# main.net
KiCad netlist of a schematic drawn in Altium Designer
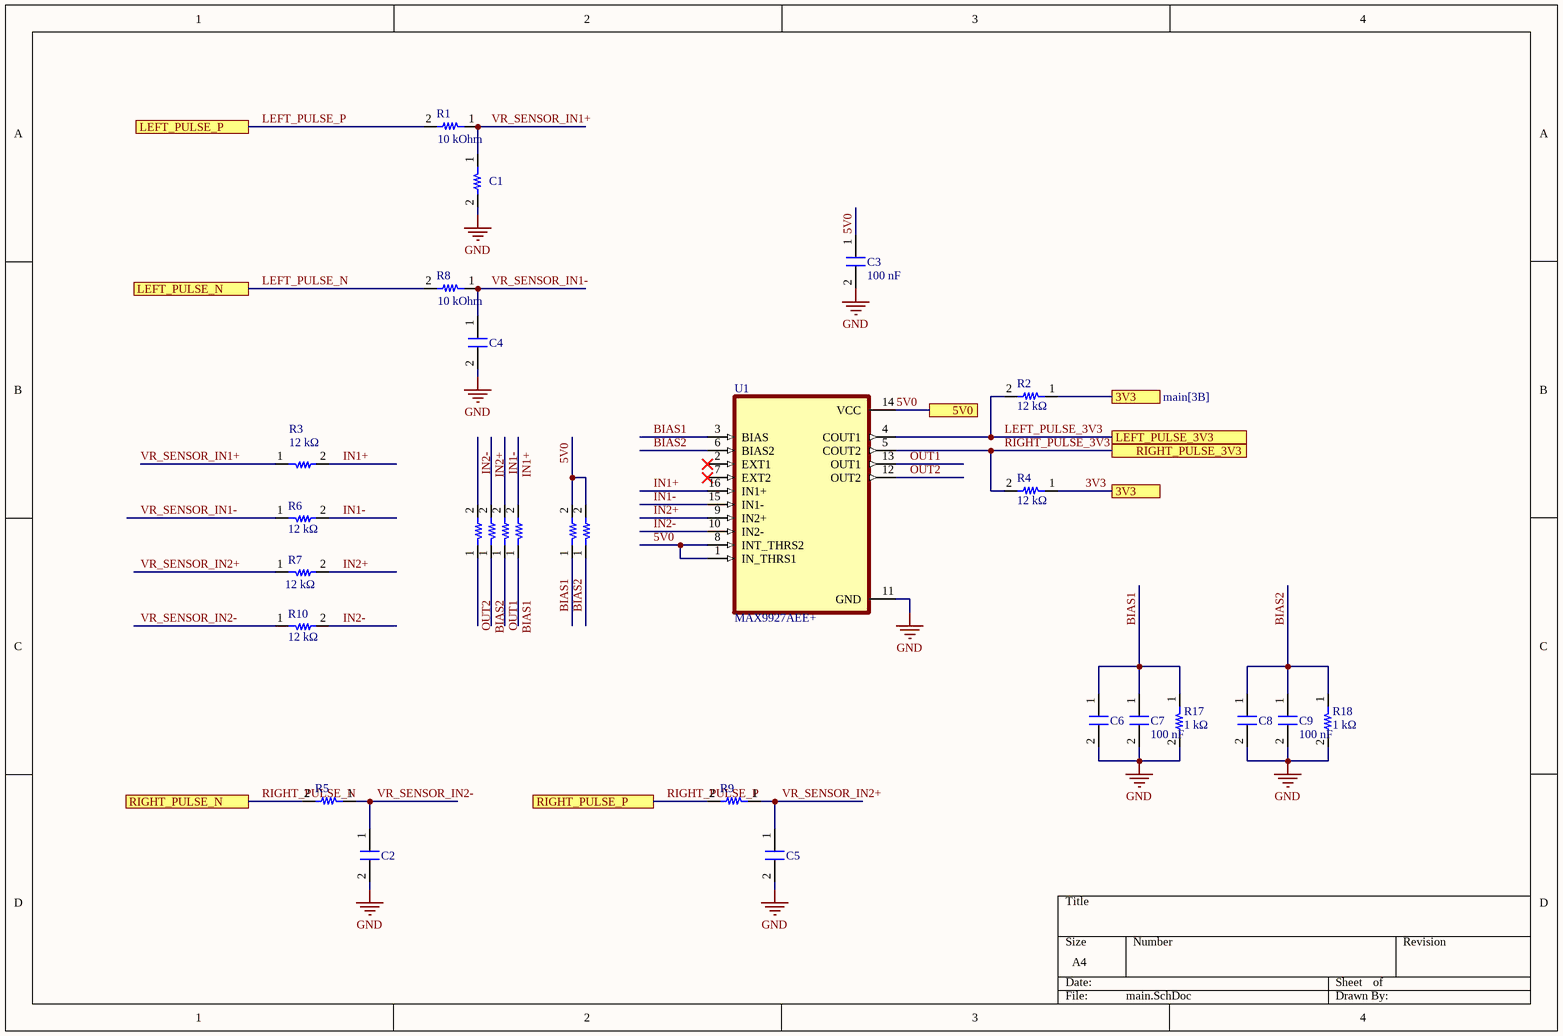
[diagram p0: main.SchDoc]

(export (version "E")
  (design (tool "Eeschema 10.0.6"))
  (components
    (comp (ref "C1")
      (value "Resistor_0402")
      (footprint "0402_fp")
      (libsource (lib "RC_sch") (part "Resistor_0402"))
    )
    (comp (ref "C2")
      (value "Capacitor_0402")
      (footprint "0402_fp")
      (libsource (lib "RC_sch") (part "Capacitor_0402"))
    )
    (comp (ref "C3")
      (value "100 nF")
      (footprint "0402_fp")
      (fields (field (name "Comment") "Capacitor_0402"))
      (libsource (lib "RC_sch") (part "Capacitor_0402"))
    )
    (comp (ref "C4")
      (value "Capacitor_0402")
      (footprint "0402_fp")
      (libsource (lib "RC_sch") (part "Capacitor_0402"))
    )
    (comp (ref "C5")
      (value "Capacitor_0402")
      (footprint "0402_fp")
      (libsource (lib "RC_sch") (part "Capacitor_0402"))
    )
    (comp (ref "C6")
      (value "Capacitor_0603")
      (footprint "0603_FP")
      (libsource (lib "RC_sch") (part "Capacitor_0603"))
    )
    (comp (ref "C7")
      (value "100 nF")
      (footprint "0402_fp")
      (fields (field (name "Comment") "Capacitor_0402"))
      (libsource (lib "RC_sch") (part "Capacitor_0402"))
    )
    (comp (ref "C8")
      (value "Capacitor_0603")
      (footprint "0603_FP")
      (libsource (lib "RC_sch") (part "Capacitor_0603"))
    )
    (comp (ref "C9")
      (value "100 nF")
      (footprint "0402_fp")
      (fields (field (name "Comment") "Capacitor_0402"))
      (libsource (lib "RC_sch") (part "Capacitor_0402"))
    )
    (comp (ref "R1")
      (value "10 kOhm")
      (footprint "0402_fp")
      (fields (field (name "Comment") "Resistor_0402"))
      (libsource (lib "RC_sch") (part "Resistor_0402"))
    )
    (comp (ref "R2")
      (value "12 kΩ")
      (footprint "0402_fp")
      (fields (field (name "Comment") "Resistor_0402"))
      (libsource (lib "RC_sch") (part "Resistor_0402"))
    )
    (comp (ref "R3")
      (value "12 kΩ")
      (footprint "0402_fp")
      (fields (field (name "Comment") "Resistor_0402"))
      (libsource (lib "RC_sch") (part "Resistor_0402"))
    )
    (comp (ref "R4")
      (value "12 kΩ")
      (footprint "0402_fp")
      (fields (field (name "Comment") "Resistor_0402"))
      (libsource (lib "RC_sch") (part "Resistor_0402"))
    )
    (comp (ref "R5")
      (value "Resistor_0402")
      (footprint "0402_fp")
      (libsource (lib "RC_sch") (part "Resistor_0402"))
    )
    (comp (ref "R6")
      (value "12 kΩ")
      (footprint "0402_fp")
      (fields (field (name "Comment") "Resistor_0402"))
      (libsource (lib "RC_sch") (part "Resistor_0402"))
    )
    (comp (ref "R7")
      (value "12 kΩ")
      (footprint "0402_fp")
      (fields (field (name "Comment") "Resistor_0402"))
      (libsource (lib "RC_sch") (part "Resistor_0402"))
    )
    (comp (ref "R8")
      (value "10 kOhm")
      (footprint "0402_fp")
      (fields (field (name "Comment") "Resistor_0402"))
      (libsource (lib "RC_sch") (part "Resistor_0402"))
    )
    (comp (ref "R9")
      (value "Resistor_0402")
      (footprint "0402_fp")
      (libsource (lib "RC_sch") (part "Resistor_0402"))
    )
    (comp (ref "R10")
      (value "12 kΩ")
      (footprint "0402_fp")
      (fields (field (name "Comment") "Resistor_0402"))
      (libsource (lib "RC_sch") (part "Resistor_0402"))
    )
    (comp (ref "R11")
      (value "Resistor_0402")
      (footprint "0402_fp")
      (libsource (lib "RC_sch") (part "Resistor_0402"))
    )
    (comp (ref "R12")
      (value "Resistor_0402")
      (footprint "0402_fp")
      (libsource (lib "RC_sch") (part "Resistor_0402"))
    )
    (comp (ref "R13")
      (value "Resistor_0402")
      (footprint "0402_fp")
      (libsource (lib "RC_sch") (part "Resistor_0402"))
    )
    (comp (ref "R14")
      (value "Resistor_0402")
      (footprint "0402_fp")
      (libsource (lib "RC_sch") (part "Resistor_0402"))
    )
    (comp (ref "R15")
      (value "Resistor_0402")
      (footprint "0402_fp")
      (libsource (lib "RC_sch") (part "Resistor_0402"))
    )
    (comp (ref "R16")
      (value "Resistor_0402")
      (footprint "0402_fp")
      (libsource (lib "RC_sch") (part "Resistor_0402"))
    )
    (comp (ref "R17")
      (value "1 kΩ")
      (footprint "0402_fp")
      (fields (field (name "Comment") "Resistor_0402"))
      (libsource (lib "RC_sch") (part "Resistor_0402"))
    )
    (comp (ref "R18")
      (value "1 kΩ")
      (footprint "0402_fp")
      (fields (field (name "Comment") "Resistor_0402"))
      (libsource (lib "RC_sch") (part "Resistor_0402"))
    )
    (comp (ref "U1")
      (value "MAX9927AEE+")
      (footprint "SOP63P602X175-16N")
      (description "Variable-Reluctance Sensor Interface with Differential Input and Adaptive Peak Threshold")
      (fields (field (name "MF") "Analog Devices"))
      (libsource (lib "MAX9927AEE_") (part "MAX9927AEE+"))
    )
  )
  (nets
    (net (code "1") (name "/3V3") (class "Default")
      (node (ref "R2") (pin "1") (pinfunction "1_1") (pintype "passive"))
      (node (ref "R4") (pin "1") (pinfunction "1_1") (pintype "passive"))
    )
    (net (code "2") (name "/5V0") (class "Default")
      (node (ref "C3") (pin "1") (pinfunction "1_1") (pintype "passive"))
      (node (ref "R15") (pin "2") (pinfunction "2_2") (pintype "passive"))
      (node (ref "R16") (pin "2") (pinfunction "2_2") (pintype "passive"))
      (node (ref "U1") (pin "1") (pinfunction "IN_THRS1_1") (pintype "input"))
      (node (ref "U1") (pin "14") (pinfunction "VCC_14") (pintype "power_in"))
      (node (ref "U1") (pin "8") (pinfunction "INT_THRS2_8") (pintype "input"))
    )
    (net (code "3") (name "/BIAS1") (class "Default")
      (node (ref "C6") (pin "1") (pinfunction "1_1") (pintype "passive"))
      (node (ref "C7") (pin "1") (pinfunction "1_1") (pintype "passive"))
      (node (ref "R14") (pin "1") (pinfunction "1_1") (pintype "passive"))
      (node (ref "R15") (pin "1") (pinfunction "1_1") (pintype "passive"))
      (node (ref "R17") (pin "1") (pinfunction "1_1") (pintype "passive"))
      (node (ref "U1") (pin "3") (pinfunction "BIAS_3") (pintype "input"))
    )
    (net (code "4") (name "/BIAS2") (class "Default")
      (node (ref "C8") (pin "1") (pinfunction "1_1") (pintype "passive"))
      (node (ref "C9") (pin "1") (pinfunction "1_1") (pintype "passive"))
      (node (ref "R12") (pin "1") (pinfunction "1_1") (pintype "passive"))
      (node (ref "R16") (pin "1") (pinfunction "1_1") (pintype "passive"))
      (node (ref "R18") (pin "1") (pinfunction "1_1") (pintype "passive"))
      (node (ref "U1") (pin "6") (pinfunction "BIAS2_6") (pintype "input"))
    )
    (net (code "5") (name "/IN1+") (class "Default")
      (node (ref "R14") (pin "2") (pinfunction "2_2") (pintype "passive"))
      (node (ref "R3") (pin "2") (pinfunction "2_2") (pintype "passive"))
      (node (ref "U1") (pin "16") (pinfunction "IN1+_16") (pintype "input"))
    )
    (net (code "6") (name "/IN1-") (class "Default")
      (node (ref "R13") (pin "2") (pinfunction "2_2") (pintype "passive"))
      (node (ref "R6") (pin "2") (pinfunction "2_2") (pintype "passive"))
      (node (ref "U1") (pin "15") (pinfunction "IN1-_15") (pintype "input"))
    )
    (net (code "7") (name "/IN2+") (class "Default")
      (node (ref "R12") (pin "2") (pinfunction "2_2") (pintype "passive"))
      (node (ref "R7") (pin "2") (pinfunction "2_2") (pintype "passive"))
      (node (ref "U1") (pin "9") (pinfunction "IN2+_9") (pintype "input"))
    )
    (net (code "8") (name "/IN2-") (class "Default")
      (node (ref "R10") (pin "2") (pinfunction "2_2") (pintype "passive"))
      (node (ref "R11") (pin "2") (pinfunction "2_2") (pintype "passive"))
      (node (ref "U1") (pin "10") (pinfunction "IN2-_10") (pintype "input"))
    )
    (net (code "9") (name "/LEFT_PULSE_3V3") (class "Default")
      (node (ref "R2") (pin "2") (pinfunction "2_2") (pintype "passive"))
      (node (ref "U1") (pin "4") (pinfunction "COUT1_4") (pintype "output"))
    )
    (net (code "10") (name "/LEFT_PULSE_N") (class "Default")
      (node (ref "R8") (pin "2") (pinfunction "2_2") (pintype "passive"))
    )
    (net (code "11") (name "/LEFT_PULSE_P") (class "Default")
      (node (ref "R1") (pin "2") (pinfunction "2_2") (pintype "passive"))
    )
    (net (code "12") (name "/OUT1") (class "Default")
      (node (ref "R13") (pin "1") (pinfunction "1_1") (pintype "passive"))
      (node (ref "U1") (pin "13") (pinfunction "OUT1_13") (pintype "output"))
    )
    (net (code "13") (name "/OUT2") (class "Default")
      (node (ref "R11") (pin "1") (pinfunction "1_1") (pintype "passive"))
      (node (ref "U1") (pin "12") (pinfunction "OUT2_12") (pintype "output"))
    )
    (net (code "14") (name "/RIGHT_PULSE_3V3") (class "Default")
      (node (ref "R4") (pin "2") (pinfunction "2_2") (pintype "passive"))
      (node (ref "U1") (pin "5") (pinfunction "COUT2_5") (pintype "output"))
    )
    (net (code "15") (name "/RIGHT_PULSE_N") (class "Default")
      (node (ref "R5") (pin "2") (pinfunction "2_2") (pintype "passive"))
    )
    (net (code "16") (name "/RIGHT_PULSE_P") (class "Default")
      (node (ref "R9") (pin "2") (pinfunction "2_2") (pintype "passive"))
    )
    (net (code "17") (name "/VR_SENSOR_IN1+") (class "Default")
      (node (ref "C1") (pin "1") (pinfunction "1_1") (pintype "passive"))
      (node (ref "R1") (pin "1") (pinfunction "1_1") (pintype "passive"))
      (node (ref "R3") (pin "1") (pinfunction "1_1") (pintype "passive"))
    )
    (net (code "18") (name "/VR_SENSOR_IN1-") (class "Default")
      (node (ref "C4") (pin "1") (pinfunction "1_1") (pintype "passive"))
      (node (ref "R6") (pin "1") (pinfunction "1_1") (pintype "passive"))
      (node (ref "R8") (pin "1") (pinfunction "1_1") (pintype "passive"))
    )
    (net (code "19") (name "/VR_SENSOR_IN2+") (class "Default")
      (node (ref "C5") (pin "1") (pinfunction "1_1") (pintype "passive"))
      (node (ref "R7") (pin "1") (pinfunction "1_1") (pintype "passive"))
      (node (ref "R9") (pin "1") (pinfunction "1_1") (pintype "passive"))
    )
    (net (code "20") (name "/VR_SENSOR_IN2-") (class "Default")
      (node (ref "C2") (pin "1") (pinfunction "1_1") (pintype "passive"))
      (node (ref "R10") (pin "1") (pinfunction "1_1") (pintype "passive"))
      (node (ref "R5") (pin "1") (pinfunction "1_1") (pintype "passive"))
    )
    (net (code "21") (name "GND") (class "Default")
      (node (ref "C1") (pin "2") (pinfunction "2_2") (pintype "passive"))
      (node (ref "C2") (pin "2") (pinfunction "2_2") (pintype "passive"))
      (node (ref "C3") (pin "2") (pinfunction "2_2") (pintype "passive"))
      (node (ref "C4") (pin "2") (pinfunction "2_2") (pintype "passive"))
      (node (ref "C5") (pin "2") (pinfunction "2_2") (pintype "passive"))
      (node (ref "C6") (pin "2") (pinfunction "2_2") (pintype "passive"))
      (node (ref "C7") (pin "2") (pinfunction "2_2") (pintype "passive"))
      (node (ref "C8") (pin "2") (pinfunction "2_2") (pintype "passive"))
      (node (ref "C9") (pin "2") (pinfunction "2_2") (pintype "passive"))
      (node (ref "R17") (pin "2") (pinfunction "2_2") (pintype "passive"))
      (node (ref "R18") (pin "2") (pinfunction "2_2") (pintype "passive"))
      (node (ref "U1") (pin "11") (pinfunction "GND_11") (pintype "power_in"))
    )
    (net (code "22") (name "unconnected-(U1-EXT1-Pad2)") (class "Default")
      (node (ref "U1") (pin "2") (pinfunction "EXT1_2") (pintype "input+no_connect"))
    )
    (net (code "23") (name "unconnected-(U1-EXT2-Pad7)") (class "Default")
      (node (ref "U1") (pin "7") (pinfunction "EXT2_7") (pintype "input+no_connect"))
    )
  )
)
